# NTC_5_Shoulder.net
KiCad netlist of a schematic drawn in Altium Designer
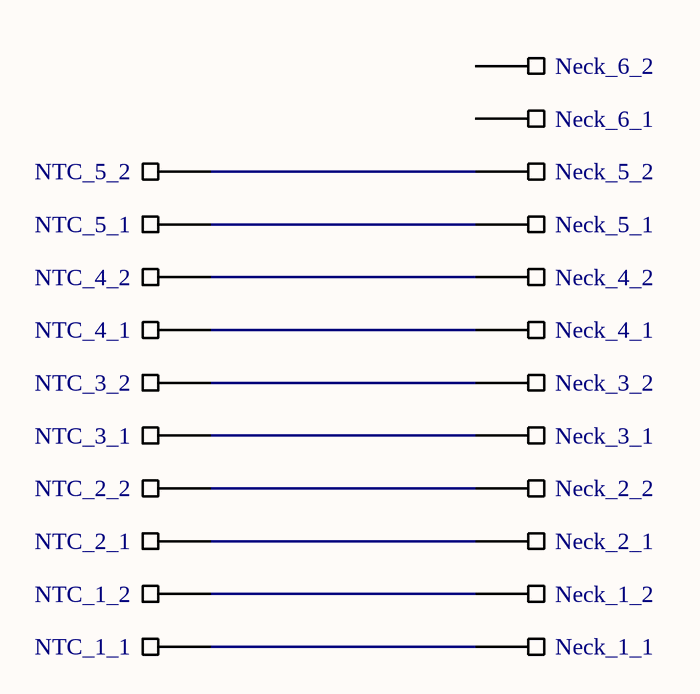
[diagram p0: NTC_5_Shoulder.SchDoc]

(export (version "E")
  (design (tool "Eeschema 10.0.6"))
  (components
    (comp (ref "Neck_1_1")
      (value "Pad")
      (footprint "Generic_Pad_1.5x1.5")
      (description "Pad 1.5mm x 1.5mm")
      (libsource (lib "libNico") (part "Generic_Pad_1.5x1.5"))
    )
    (comp (ref "Neck_1_2")
      (value "Pad")
      (footprint "Generic_Pad_1.5x1.5")
      (description "Pad 1.5mm x 1.5mm")
      (libsource (lib "libNico") (part "Generic_Pad_1.5x1.5"))
    )
    (comp (ref "Neck_2_1")
      (value "Pad")
      (footprint "Generic_Pad_1.5x1.5")
      (description "Pad 1.5mm x 1.5mm")
      (libsource (lib "libNico") (part "Generic_Pad_1.5x1.5"))
    )
    (comp (ref "Neck_2_2")
      (value "Pad")
      (footprint "Generic_Pad_1.5x1.5")
      (description "Pad 1.5mm x 1.5mm")
      (libsource (lib "libNico") (part "Generic_Pad_1.5x1.5"))
    )
    (comp (ref "Neck_3_1")
      (value "Pad")
      (footprint "Generic_Pad_1.5x1.5")
      (description "Pad 1.5mm x 1.5mm")
      (libsource (lib "libNico") (part "Generic_Pad_1.5x1.5"))
    )
    (comp (ref "Neck_3_2")
      (value "Pad")
      (footprint "Generic_Pad_1.5x1.5")
      (description "Pad 1.5mm x 1.5mm")
      (libsource (lib "libNico") (part "Generic_Pad_1.5x1.5"))
    )
    (comp (ref "Neck_4_1")
      (value "Pad")
      (footprint "Generic_Pad_1.5x1.5")
      (description "Pad 1.5mm x 1.5mm")
      (libsource (lib "libNico") (part "Generic_Pad_1.5x1.5"))
    )
    (comp (ref "Neck_4_2")
      (value "Pad")
      (footprint "Generic_Pad_1.5x1.5")
      (description "Pad 1.5mm x 1.5mm")
      (libsource (lib "libNico") (part "Generic_Pad_1.5x1.5"))
    )
    (comp (ref "Neck_5_1")
      (value "Pad")
      (footprint "Generic_Pad_1.5x1.5")
      (description "Pad 1.5mm x 1.5mm")
      (libsource (lib "libNico") (part "Generic_Pad_1.5x1.5"))
    )
    (comp (ref "Neck_5_2")
      (value "Pad")
      (footprint "Generic_Pad_1.5x1.5")
      (description "Pad 1.5mm x 1.5mm")
      (libsource (lib "libNico") (part "Generic_Pad_1.5x1.5"))
    )
    (comp (ref "Neck_6_1")
      (value "Pad")
      (footprint "Generic_Pad_1.5x1.5")
      (description "Pad 1.5mm x 1.5mm")
      (libsource (lib "libNico") (part "Generic_Pad_1.5x1.5"))
    )
    (comp (ref "Neck_6_2")
      (value "Pad")
      (footprint "Generic_Pad_1.5x1.5")
      (description "Pad 1.5mm x 1.5mm")
      (libsource (lib "libNico") (part "Generic_Pad_1.5x1.5"))
    )
    (comp (ref "NTC_1_1")
      (value "Pad")
      (footprint "Generic_Pad_1.5x1.5")
      (description "Pad 1.5mm x 1.5mm")
      (libsource (lib "libNico") (part "Generic_Pad_1.5x1.5"))
    )
    (comp (ref "NTC_1_2")
      (value "Pad")
      (footprint "Generic_Pad_1.5x1.5")
      (description "Pad 1.5mm x 1.5mm")
      (libsource (lib "libNico") (part "Generic_Pad_1.5x1.5"))
    )
    (comp (ref "NTC_2_1")
      (value "Pad")
      (footprint "Generic_Pad_1.5x1.5")
      (description "Pad 1.5mm x 1.5mm")
      (libsource (lib "libNico") (part "Generic_Pad_1.5x1.5"))
    )
    (comp (ref "NTC_2_2")
      (value "Pad")
      (footprint "Generic_Pad_1.5x1.5")
      (description "Pad 1.5mm x 1.5mm")
      (libsource (lib "libNico") (part "Generic_Pad_1.5x1.5"))
    )
    (comp (ref "NTC_3_1")
      (value "Pad")
      (footprint "Generic_Pad_1.5x1.5")
      (description "Pad 1.5mm x 1.5mm")
      (libsource (lib "libNico") (part "Generic_Pad_1.5x1.5"))
    )
    (comp (ref "NTC_3_2")
      (value "Pad")
      (footprint "Generic_Pad_1.5x1.5")
      (description "Pad 1.5mm x 1.5mm")
      (libsource (lib "libNico") (part "Generic_Pad_1.5x1.5"))
    )
    (comp (ref "NTC_4_1")
      (value "Pad")
      (footprint "Generic_Pad_1.5x1.5")
      (description "Pad 1.5mm x 1.5mm")
      (libsource (lib "libNico") (part "Generic_Pad_1.5x1.5"))
    )
    (comp (ref "NTC_4_2")
      (value "Pad")
      (footprint "Generic_Pad_1.5x1.5")
      (description "Pad 1.5mm x 1.5mm")
      (libsource (lib "libNico") (part "Generic_Pad_1.5x1.5"))
    )
    (comp (ref "NTC_5_1")
      (value "Pad")
      (footprint "Generic_Pad_1.5x1.5")
      (description "Pad 1.5mm x 1.5mm")
      (libsource (lib "libNico") (part "Generic_Pad_1.5x1.5"))
    )
    (comp (ref "NTC_5_2")
      (value "Pad")
      (footprint "Generic_Pad_1.5x1.5")
      (description "Pad 1.5mm x 1.5mm")
      (libsource (lib "libNico") (part "Generic_Pad_1.5x1.5"))
    )
  )
  (nets
    (net (code "1") (name "Net-(NTC_1_1-Pad)") (class "Default")
      (node (ref "NTC_1_1") (pin "P") (pinfunction "Pad_P") (pintype "passive"))
      (node (ref "Neck_1_1") (pin "P") (pinfunction "Pad_P") (pintype "passive"))
    )
    (net (code "2") (name "Net-(NTC_1_2-Pad)") (class "Default")
      (node (ref "NTC_1_2") (pin "P") (pinfunction "Pad_P") (pintype "passive"))
      (node (ref "Neck_1_2") (pin "P") (pinfunction "Pad_P") (pintype "passive"))
    )
    (net (code "3") (name "Net-(NTC_2_1-Pad)") (class "Default")
      (node (ref "NTC_2_1") (pin "P") (pinfunction "Pad_P") (pintype "passive"))
      (node (ref "Neck_2_1") (pin "P") (pinfunction "Pad_P") (pintype "passive"))
    )
    (net (code "4") (name "Net-(NTC_2_2-Pad)") (class "Default")
      (node (ref "NTC_2_2") (pin "P") (pinfunction "Pad_P") (pintype "passive"))
      (node (ref "Neck_2_2") (pin "P") (pinfunction "Pad_P") (pintype "passive"))
    )
    (net (code "5") (name "Net-(NTC_3_1-Pad)") (class "Default")
      (node (ref "NTC_3_1") (pin "P") (pinfunction "Pad_P") (pintype "passive"))
      (node (ref "Neck_3_1") (pin "P") (pinfunction "Pad_P") (pintype "passive"))
    )
    (net (code "6") (name "Net-(NTC_3_2-Pad)") (class "Default")
      (node (ref "NTC_3_2") (pin "P") (pinfunction "Pad_P") (pintype "passive"))
      (node (ref "Neck_3_2") (pin "P") (pinfunction "Pad_P") (pintype "passive"))
    )
    (net (code "7") (name "Net-(NTC_4_1-Pad)") (class "Default")
      (node (ref "NTC_4_1") (pin "P") (pinfunction "Pad_P") (pintype "passive"))
      (node (ref "Neck_4_1") (pin "P") (pinfunction "Pad_P") (pintype "passive"))
    )
    (net (code "8") (name "Net-(NTC_4_2-Pad)") (class "Default")
      (node (ref "NTC_4_2") (pin "P") (pinfunction "Pad_P") (pintype "passive"))
      (node (ref "Neck_4_2") (pin "P") (pinfunction "Pad_P") (pintype "passive"))
    )
    (net (code "9") (name "Net-(NTC_5_1-Pad)") (class "Default")
      (node (ref "NTC_5_1") (pin "P") (pinfunction "Pad_P") (pintype "passive"))
      (node (ref "Neck_5_1") (pin "P") (pinfunction "Pad_P") (pintype "passive"))
    )
    (net (code "10") (name "Net-(NTC_5_2-Pad)") (class "Default")
      (node (ref "NTC_5_2") (pin "P") (pinfunction "Pad_P") (pintype "passive"))
      (node (ref "Neck_5_2") (pin "P") (pinfunction "Pad_P") (pintype "passive"))
    )
    (net (code "11") (name "unconnected-(Neck_6_1-Pad-PadP)") (class "Default")
      (node (ref "Neck_6_1") (pin "P") (pinfunction "Pad_P") (pintype "passive"))
    )
    (net (code "12") (name "unconnected-(Neck_6_2-Pad-PadP)") (class "Default")
      (node (ref "Neck_6_2") (pin "P") (pinfunction "Pad_P") (pintype "passive"))
    )
  )
)
